# ctrl_board.net
KiCad netlist of a schematic drawn in EAGLE
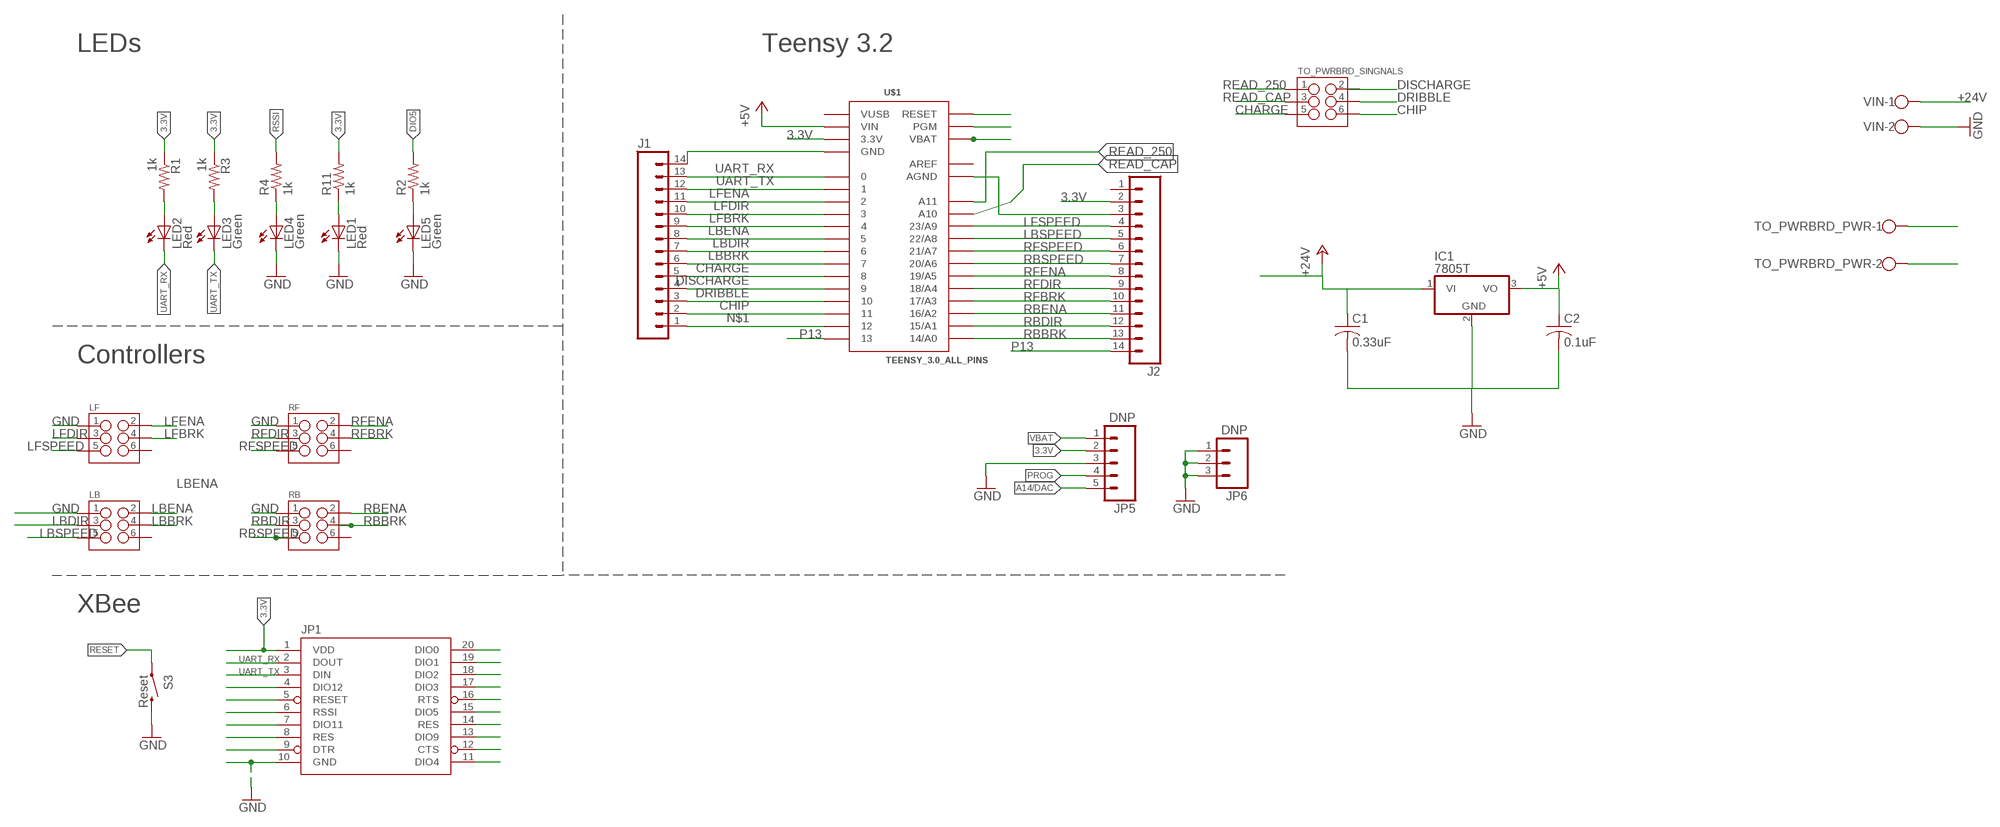
[diagram p0: schematic, sheet 1]

(export (version "E")
  (design (tool "Eeschema 10.0.6"))
  (components
    (comp (ref "C1")
      (value "0.33uF")
      (footprint "eagle-import:C0805")
      (libsource (lib "eagle-import") (part "C-USC0805"))
    )
    (comp (ref "C2")
      (value "0.1uF")
      (footprint "eagle-import:C0805")
      (libsource (lib "eagle-import") (part "C-USC0805"))
    )
    (comp (ref "IC1")
      (value "7805T")
      (footprint "eagle-import:TO220H")
      (libsource (lib "eagle-import") (part "78T05"))
    )
    (comp (ref "J1")
      (value "M14")
      (footprint "eagle-import:1X14")
      (libsource (lib "eagle-import") (part "M14"))
    )
    (comp (ref "J2")
      (value "M14")
      (footprint "eagle-import:1X14")
      (libsource (lib "eagle-import") (part "M14"))
    )
    (comp (ref "JP1")
      (value "XBEE-1B1")
      (footprint "eagle-import:XBEE-1")
      (libsource (lib "eagle-import") (part "XBEE-1B1"))
    )
    (comp (ref "JP5")
      (value "DNP")
      (footprint "eagle-import:1X05")
      (libsource (lib "eagle-import") (part "M05PTH"))
    )
    (comp (ref "JP6")
      (value "DNP")
      (footprint "eagle-import:1X03")
      (libsource (lib "eagle-import") (part "M03PTH"))
    )
    (comp (ref "LB")
      (value "M03X2POGO_PINS")
      (footprint "eagle-import:2X3_POGO")
      (libsource (lib "eagle-import") (part "M03X2POGO_PINS"))
    )
    (comp (ref "LED1")
      (value "Red")
      (footprint "eagle-import:LED-0603")
      (libsource (lib "eagle-import") (part "LED-RED0603"))
    )
    (comp (ref "LED2")
      (value "Red")
      (footprint "eagle-import:LED-0603")
      (libsource (lib "eagle-import") (part "LED-RED0603"))
    )
    (comp (ref "LED3")
      (value "Green")
      (footprint "eagle-import:LED-0603")
      (libsource (lib "eagle-import") (part "LED-GREEN0603"))
    )
    (comp (ref "LED4")
      (value "Green")
      (footprint "eagle-import:LED-0603")
      (libsource (lib "eagle-import") (part "LED-GREEN0603"))
    )
    (comp (ref "LED5")
      (value "Green")
      (footprint "eagle-import:LED-0603")
      (libsource (lib "eagle-import") (part "LED-GREEN0603"))
    )
    (comp (ref "LF")
      (value "M03X2POGO_PINS")
      (footprint "eagle-import:2X3_POGO")
      (libsource (lib "eagle-import") (part "M03X2POGO_PINS"))
    )
    (comp (ref "R1")
      (value "1k")
      (footprint "eagle-import:0603-RES")
      (libsource (lib "eagle-import") (part "1KOHM1/10W1%(0603)"))
    )
    (comp (ref "R2")
      (value "1k")
      (footprint "eagle-import:0603-RES")
      (libsource (lib "eagle-import") (part "1KOHM1/10W1%(0603)"))
    )
    (comp (ref "R3")
      (value "1k")
      (footprint "eagle-import:0603-RES")
      (libsource (lib "eagle-import") (part "1KOHM1/10W1%(0603)"))
    )
    (comp (ref "R4")
      (value "1k")
      (footprint "eagle-import:0603-RES")
      (libsource (lib "eagle-import") (part "1KOHM1/10W1%(0603)"))
    )
    (comp (ref "R11")
      (value "1k")
      (footprint "eagle-import:0603-RES")
      (libsource (lib "eagle-import") (part "1KOHM1/10W1%(0603)"))
    )
    (comp (ref "RB")
      (value "M03X2POGO_PINS")
      (footprint "eagle-import:2X3_POGO")
      (libsource (lib "eagle-import") (part "M03X2POGO_PINS"))
    )
    (comp (ref "RF")
      (value "M03X2POGO_PINS")
      (footprint "eagle-import:2X3_POGO")
      (libsource (lib "eagle-import") (part "M03X2POGO_PINS"))
    )
    (comp (ref "S3")
      (value "Reset")
      (footprint "eagle-import:TACTILE-SWITCH-SMD")
      (libsource (lib "eagle-import") (part "SWITCH-MOMENTARY-2SMD"))
    )
    (comp (ref "TO_PWRBRD_PWR")
      (value "W237-102")
      (footprint "eagle-import:W237-102")
      (fields (field (name "MPN") "237-102"))
      (libsource (lib "eagle-import") (part "W237-102"))
    )
    (comp (ref "TO_PWRBRD_SINGNALS")
      (value "M03X2POGO_PINS")
      (footprint "eagle-import:2X3_POGO")
      (libsource (lib "eagle-import") (part "M03X2POGO_PINS"))
    )
    (comp (ref "U$1")
      (value "TEENSY_3.0_ALL_PINS")
      (footprint "eagle-import:TEENSY3-ALL_PINS")
      (libsource (lib "eagle-import") (part "TEENSY_3.0_ALL_PINS"))
    )
    (comp (ref "VIN")
      (value "W237-102")
      (footprint "eagle-import:W237-102")
      (fields (field (name "MPN") "237-102"))
      (libsource (lib "eagle-import") (part "W237-102"))
    )
  )
  (nets
    (net (code "1") (name "+5V") (class "Default")
      (node (ref "C2") (pin "1") (pinfunction "1_1") (pintype "passive"))
      (node (ref "IC1") (pin "3") (pinfunction "VO_3") (pintype "passive"))
      (node (ref "U$1") (pin "VIN") (pinfunction "VIN_VIN") (pintype "power_in"))
    )
    (net (code "2") (name "+24V") (class "Default")
      (node (ref "C1") (pin "1") (pinfunction "1_1") (pintype "passive"))
      (node (ref "IC1") (pin "1") (pinfunction "VI_1") (pintype "input"))
      (node (ref "TO_PWRBRD_PWR") (pin "1") (pinfunction "KL_1") (pintype "passive"))
      (node (ref "VIN") (pin "1") (pinfunction "KL_1") (pintype "passive"))
    )
    (net (code "3") (name "/AREF") (class "Default")
      (node (ref "U$1") (pin "AREF") (pinfunction "AREF_AREF") (pintype "power_in"))
    )
    (net (code "4") (name "/CHARGE") (class "Default")
      (node (ref "J1") (pin "5") (pinfunction "5_5") (pintype "passive"))
      (node (ref "TO_PWRBRD_SINGNALS") (pin "P$5") (pinfunction "5_P$5") (pintype "bidirectional"))
      (node (ref "U$1") (pin "8") (pinfunction "8_8") (pintype "bidirectional"))
    )
    (net (code "5") (name "/CHIP") (class "Default")
      (node (ref "J1") (pin "2") (pinfunction "2_2") (pintype "passive"))
      (node (ref "TO_PWRBRD_SINGNALS") (pin "P$6") (pinfunction "6_P$6") (pintype "bidirectional"))
      (node (ref "U$1") (pin "11") (pinfunction "11_11") (pintype "bidirectional"))
    )
    (net (code "6") (name "/DISCHARGE") (class "Default")
      (node (ref "J1") (pin "4") (pinfunction "4_4") (pintype "passive"))
      (node (ref "U$1") (pin "9") (pinfunction "9_9") (pintype "bidirectional"))
    )
    (net (code "7") (name "/DRIBBLE") (class "Default")
      (node (ref "J1") (pin "3") (pinfunction "3_3") (pintype "passive"))
      (node (ref "TO_PWRBRD_SINGNALS") (pin "P$4") (pinfunction "4_P$4") (pintype "bidirectional"))
      (node (ref "U$1") (pin "10") (pinfunction "10_10") (pintype "bidirectional"))
    )
    (net (code "8") (name "/LBBRK") (class "Default")
      (node (ref "J1") (pin "6") (pinfunction "6_6") (pintype "passive"))
      (node (ref "LB") (pin "P$4") (pinfunction "4_P$4") (pintype "bidirectional"))
      (node (ref "U$1") (pin "7") (pinfunction "7_7") (pintype "bidirectional"))
    )
    (net (code "9") (name "/LBDIR") (class "Default")
      (node (ref "J1") (pin "7") (pinfunction "7_7") (pintype "passive"))
      (node (ref "LB") (pin "P$3") (pinfunction "3_P$3") (pintype "bidirectional"))
      (node (ref "U$1") (pin "6") (pinfunction "6_6") (pintype "bidirectional"))
    )
    (net (code "10") (name "/LBENA") (class "Default")
      (node (ref "J1") (pin "8") (pinfunction "8_8") (pintype "passive"))
      (node (ref "LB") (pin "P$2") (pinfunction "2_P$2") (pintype "bidirectional"))
      (node (ref "U$1") (pin "5") (pinfunction "5_5") (pintype "bidirectional"))
    )
    (net (code "11") (name "/LBSPEED") (class "Default")
      (node (ref "J2") (pin "5") (pinfunction "5_5") (pintype "passive"))
      (node (ref "LB") (pin "P$5") (pinfunction "5_P$5") (pintype "bidirectional"))
      (node (ref "U$1") (pin "22/A8") (pinfunction "22/A8_22/A8") (pintype "bidirectional"))
    )
    (net (code "12") (name "/LFBRK") (class "Default")
      (node (ref "J1") (pin "9") (pinfunction "9_9") (pintype "passive"))
      (node (ref "LF") (pin "P$4") (pinfunction "4_P$4") (pintype "bidirectional"))
      (node (ref "U$1") (pin "4") (pinfunction "4_4") (pintype "bidirectional"))
    )
    (net (code "13") (name "/LFDIR") (class "Default")
      (node (ref "J1") (pin "10") (pinfunction "10_10") (pintype "passive"))
      (node (ref "LF") (pin "P$3") (pinfunction "3_P$3") (pintype "bidirectional"))
      (node (ref "U$1") (pin "3") (pinfunction "3_3") (pintype "bidirectional"))
    )
    (net (code "14") (name "/LFENA") (class "Default")
      (node (ref "J1") (pin "11") (pinfunction "11_11") (pintype "passive"))
      (node (ref "LF") (pin "P$2") (pinfunction "2_P$2") (pintype "bidirectional"))
      (node (ref "U$1") (pin "2") (pinfunction "2_2") (pintype "bidirectional"))
    )
    (net (code "15") (name "/LFSPEED") (class "Default")
      (node (ref "J2") (pin "4") (pinfunction "4_4") (pintype "passive"))
      (node (ref "LF") (pin "P$5") (pinfunction "5_P$5") (pintype "bidirectional"))
      (node (ref "U$1") (pin "23/A9") (pinfunction "23/A9_23/A9") (pintype "bidirectional"))
    )
    (net (code "16") (name "/N$1") (class "Default")
      (node (ref "J1") (pin "1") (pinfunction "1_1") (pintype "passive"))
      (node (ref "U$1") (pin "12") (pinfunction "12_12") (pintype "bidirectional"))
    )
    (net (code "17") (name "/P13") (class "Default")
      (node (ref "J2") (pin "14") (pinfunction "14_14") (pintype "passive"))
      (node (ref "U$1") (pin "13") (pinfunction "13_13") (pintype "bidirectional"))
    )
    (net (code "18") (name "/RBBRK") (class "Default")
      (node (ref "J2") (pin "13") (pinfunction "13_13") (pintype "passive"))
      (node (ref "RB") (pin "P$4") (pinfunction "4_P$4") (pintype "bidirectional"))
      (node (ref "U$1") (pin "14/A0") (pinfunction "14/A0_14/A0") (pintype "bidirectional"))
    )
    (net (code "19") (name "/RBDIR") (class "Default")
      (node (ref "J2") (pin "12") (pinfunction "12_12") (pintype "passive"))
      (node (ref "RB") (pin "P$3") (pinfunction "3_P$3") (pintype "bidirectional"))
      (node (ref "U$1") (pin "15/A1") (pinfunction "15/A1_15/A1") (pintype "bidirectional"))
    )
    (net (code "20") (name "/RBENA") (class "Default")
      (node (ref "J2") (pin "11") (pinfunction "11_11") (pintype "passive"))
      (node (ref "RB") (pin "P$2") (pinfunction "2_P$2") (pintype "bidirectional"))
      (node (ref "U$1") (pin "16/A2") (pinfunction "16/A2_16/A2") (pintype "bidirectional"))
    )
    (net (code "21") (name "/RBSPEED") (class "Default")
      (node (ref "J2") (pin "7") (pinfunction "7_7") (pintype "passive"))
      (node (ref "RB") (pin "P$5") (pinfunction "5_P$5") (pintype "bidirectional"))
      (node (ref "U$1") (pin "20/A6") (pinfunction "20/A6_20/A6") (pintype "bidirectional"))
    )
    (net (code "22") (name "/RFBRK") (class "Default")
      (node (ref "J2") (pin "10") (pinfunction "10_10") (pintype "passive"))
      (node (ref "RF") (pin "P$4") (pinfunction "4_P$4") (pintype "bidirectional"))
      (node (ref "U$1") (pin "17/A3") (pinfunction "17/A3_17/A3") (pintype "bidirectional"))
    )
    (net (code "23") (name "/RFDIR") (class "Default")
      (node (ref "J2") (pin "9") (pinfunction "9_9") (pintype "passive"))
      (node (ref "RF") (pin "P$3") (pinfunction "3_P$3") (pintype "bidirectional"))
      (node (ref "U$1") (pin "18/A4") (pinfunction "18/A4_18/A4") (pintype "bidirectional"))
    )
    (net (code "24") (name "/RFENA") (class "Default")
      (node (ref "J2") (pin "8") (pinfunction "8_8") (pintype "passive"))
      (node (ref "RF") (pin "P$2") (pinfunction "2_P$2") (pintype "bidirectional"))
      (node (ref "U$1") (pin "19/A5") (pinfunction "19/A5_19/A5") (pintype "bidirectional"))
    )
    (net (code "25") (name "/RFSPEED") (class "Default")
      (node (ref "J2") (pin "6") (pinfunction "6_6") (pintype "passive"))
      (node (ref "RF") (pin "P$5") (pinfunction "5_P$5") (pintype "bidirectional"))
      (node (ref "U$1") (pin "21/A7") (pinfunction "21/A7_21/A7") (pintype "bidirectional"))
    )
    (net (code "26") (name "/VUSB") (class "Default")
      (node (ref "U$1") (pin "VUSB") (pinfunction "VUSB_VUSB") (pintype "power_in"))
    )
    (net (code "27") (name "3.3V") (class "Default")
      (node (ref "J2") (pin "2") (pinfunction "2_2") (pintype "passive"))
      (node (ref "JP1") (pin "1") (pinfunction "VDD_1") (pintype "power_in"))
      (node (ref "JP5") (pin "2") (pinfunction "2_2") (pintype "passive"))
      (node (ref "R1") (pin "1") (pinfunction "1_1") (pintype "passive"))
      (node (ref "R11") (pin "2") (pinfunction "2_2") (pintype "passive"))
      (node (ref "R3") (pin "1") (pinfunction "1_1") (pintype "passive"))
      (node (ref "U$1") (pin "3.3V") (pinfunction "3.3V_3.3V") (pintype "power_in"))
      (node (ref "U$1") (pin "3.3V1") (pinfunction "3.3V_3.3V1") (pintype "power_in"))
    )
    (net (code "28") (name "A14{slash}DAC") (class "Default")
      (node (ref "JP5") (pin "5") (pinfunction "5_5") (pintype "passive"))
      (node (ref "U$1") (pin "RESET/DAC") (pinfunction "RESET_RESET/DAC") (pintype "bidirectional"))
    )
    (net (code "29") (name "DIO5") (class "Default")
      (node (ref "JP1") (pin "15") (pinfunction "DIO5_15") (pintype "bidirectional"))
      (node (ref "R2") (pin "2") (pinfunction "2_2") (pintype "passive"))
    )
    (net (code "30") (name "GND") (class "Default")
      (node (ref "C1") (pin "2") (pinfunction "2_2") (pintype "passive"))
      (node (ref "C2") (pin "2") (pinfunction "2_2") (pintype "passive"))
      (node (ref "IC1") (pin "2") (pinfunction "GND_2") (pintype "passive"))
      (node (ref "J1") (pin "14") (pinfunction "14_14") (pintype "passive"))
      (node (ref "JP1") (pin "10") (pinfunction "GND_10") (pintype "power_in"))
      (node (ref "JP5") (pin "3") (pinfunction "3_3") (pintype "passive"))
      (node (ref "JP6") (pin "1") (pinfunction "1_1") (pintype "passive"))
      (node (ref "JP6") (pin "2") (pinfunction "2_2") (pintype "passive"))
      (node (ref "JP6") (pin "3") (pinfunction "3_3") (pintype "passive"))
      (node (ref "LB") (pin "P$1") (pinfunction "1_P$1") (pintype "bidirectional"))
      (node (ref "LED1") (pin "C") (pinfunction "C_C") (pintype "passive"))
      (node (ref "LED4") (pin "C") (pinfunction "C_C") (pintype "passive"))
      (node (ref "LED5") (pin "C") (pinfunction "C_C") (pintype "passive"))
      (node (ref "LF") (pin "P$1") (pinfunction "1_P$1") (pintype "bidirectional"))
      (node (ref "RB") (pin "P$1") (pinfunction "1_P$1") (pintype "bidirectional"))
      (node (ref "RF") (pin "P$1") (pinfunction "1_P$1") (pintype "bidirectional"))
      (node (ref "S3") (pin "3") (pinfunction "2_3") (pintype "passive"))
      (node (ref "TO_PWRBRD_PWR") (pin "2") (pinfunction "KL_2") (pintype "passive"))
      (node (ref "U$1") (pin "GND") (pinfunction "GND_GND") (pintype "power_in"))
      (node (ref "U$1") (pin "GND1") (pinfunction "GND_GND1") (pintype "power_in"))
      (node (ref "VIN") (pin "2") (pinfunction "KL_2") (pintype "passive"))
    )
    (net (code "31") (name "Net-(J2-Pad3)") (class "Default")
      (node (ref "J2") (pin "3") (pinfunction "3_3") (pintype "passive"))
      (node (ref "U$1") (pin "AGND") (pinfunction "AGND_AGND") (pintype "power_in"))
    )
    (net (code "32") (name "Net-(LED1-PadA)") (class "Default")
      (node (ref "LED1") (pin "A") (pinfunction "A_A") (pintype "passive"))
      (node (ref "R11") (pin "1") (pinfunction "1_1") (pintype "passive"))
    )
    (net (code "33") (name "Net-(LED2-PadA)") (class "Default")
      (node (ref "LED2") (pin "A") (pinfunction "A_A") (pintype "passive"))
      (node (ref "R1") (pin "2") (pinfunction "2_2") (pintype "passive"))
    )
    (net (code "34") (name "Net-(LED3-PadA)") (class "Default")
      (node (ref "LED3") (pin "A") (pinfunction "A_A") (pintype "passive"))
      (node (ref "R3") (pin "2") (pinfunction "2_2") (pintype "passive"))
    )
    (net (code "35") (name "Net-(LED4-PadA)") (class "Default")
      (node (ref "LED4") (pin "A") (pinfunction "A_A") (pintype "passive"))
      (node (ref "R4") (pin "1") (pinfunction "1_1") (pintype "passive"))
    )
    (net (code "36") (name "Net-(LED5-PadA)") (class "Default")
      (node (ref "LED5") (pin "A") (pinfunction "A_A") (pintype "passive"))
      (node (ref "R2") (pin "1") (pinfunction "1_1") (pintype "passive"))
    )
    (net (code "37") (name "PROG") (class "Default")
      (node (ref "JP5") (pin "4") (pinfunction "4_4") (pintype "passive"))
      (node (ref "U$1") (pin "PGM") (pinfunction "PGM_PGM") (pintype "bidirectional"))
    )
    (net (code "38") (name "READ_250") (class "Default")
      (node (ref "TO_PWRBRD_SINGNALS") (pin "P$1") (pinfunction "1_P$1") (pintype "bidirectional"))
      (node (ref "U$1") (pin "A11") (pinfunction "A11_A11") (pintype "bidirectional"))
    )
    (net (code "39") (name "READ_CAP") (class "Default")
      (node (ref "TO_PWRBRD_SINGNALS") (pin "P$3") (pinfunction "3_P$3") (pintype "bidirectional"))
      (node (ref "U$1") (pin "A10") (pinfunction "A10_A10") (pintype "bidirectional"))
    )
    (net (code "40") (name "RESET") (class "Default")
      (node (ref "JP1") (pin "5") (pinfunction "RESET_5") (pintype "input"))
      (node (ref "S3") (pin "1") (pinfunction "1_1") (pintype "passive"))
    )
    (net (code "41") (name "RSSI") (class "Default")
      (node (ref "JP1") (pin "6") (pinfunction "RSSI_6") (pintype "bidirectional"))
      (node (ref "R4") (pin "2") (pinfunction "2_2") (pintype "passive"))
    )
    (net (code "42") (name "UART_RX") (class "Default")
      (node (ref "J1") (pin "13") (pinfunction "13_13") (pintype "passive"))
      (node (ref "JP1") (pin "2") (pinfunction "DOUT_2") (pintype "output"))
      (node (ref "LED2") (pin "C") (pinfunction "C_C") (pintype "passive"))
      (node (ref "U$1") (pin "0") (pinfunction "0_0") (pintype "bidirectional"))
    )
    (net (code "43") (name "UART_TX") (class "Default")
      (node (ref "J1") (pin "12") (pinfunction "12_12") (pintype "passive"))
      (node (ref "JP1") (pin "3") (pinfunction "DIN_3") (pintype "input"))
      (node (ref "LED3") (pin "C") (pinfunction "C_C") (pintype "passive"))
      (node (ref "U$1") (pin "1") (pinfunction "1_1") (pintype "bidirectional"))
    )
    (net (code "44") (name "VBAT") (class "Default")
      (node (ref "JP5") (pin "1") (pinfunction "1_1") (pintype "passive"))
      (node (ref "U$1") (pin "VBAT") (pinfunction "VBAT_VBAT") (pintype "power_in"))
    )
    (net (code "45") (name "unconnected-(J2-Pad1)") (class "Default")
      (node (ref "J2") (pin "1") (pinfunction "1_1") (pintype "passive"))
    )
    (net (code "46") (name "unconnected-(JP1-CTS-Pad12)") (class "Default")
      (node (ref "JP1") (pin "12") (pinfunction "CTS_12") (pintype "output"))
    )
    (net (code "47") (name "unconnected-(JP1-DIO0-Pad20)") (class "Default")
      (node (ref "JP1") (pin "20") (pinfunction "DIO0_20") (pintype "bidirectional"))
    )
    (net (code "48") (name "unconnected-(JP1-DIO1-Pad19)") (class "Default")
      (node (ref "JP1") (pin "19") (pinfunction "DIO1_19") (pintype "bidirectional"))
    )
    (net (code "49") (name "unconnected-(JP1-DIO2-Pad18)") (class "Default")
      (node (ref "JP1") (pin "18") (pinfunction "DIO2_18") (pintype "bidirectional"))
    )
    (net (code "50") (name "unconnected-(JP1-DIO3-Pad17)") (class "Default")
      (node (ref "JP1") (pin "17") (pinfunction "DIO3_17") (pintype "bidirectional"))
    )
    (net (code "51") (name "unconnected-(JP1-DIO4-Pad11)") (class "Default")
      (node (ref "JP1") (pin "11") (pinfunction "DIO4_11") (pintype "bidirectional"))
    )
    (net (code "52") (name "unconnected-(JP1-DIO9-Pad13)") (class "Default")
      (node (ref "JP1") (pin "13") (pinfunction "DIO9_13") (pintype "bidirectional"))
    )
    (net (code "53") (name "unconnected-(JP1-DIO11-Pad7)") (class "Default")
      (node (ref "JP1") (pin "7") (pinfunction "DIO11_7") (pintype "bidirectional"))
    )
    (net (code "54") (name "unconnected-(JP1-DIO12-Pad4)") (class "Default")
      (node (ref "JP1") (pin "4") (pinfunction "DIO12_4") (pintype "bidirectional"))
    )
    (net (code "55") (name "unconnected-(JP1-DTR-Pad9)") (class "Default")
      (node (ref "JP1") (pin "9") (pinfunction "DTR_9") (pintype "bidirectional"))
    )
    (net (code "56") (name "unconnected-(JP1-RES-Pad8)") (class "Default")
      (node (ref "JP1") (pin "8") (pinfunction "RES_8") (pintype "bidirectional"))
    )
    (net (code "57") (name "unconnected-(JP1-RES-Pad14)") (class "Default")
      (node (ref "JP1") (pin "14") (pinfunction "RES_14") (pintype "bidirectional"))
    )
    (net (code "58") (name "unconnected-(JP1-RTS-Pad16)") (class "Default")
      (node (ref "JP1") (pin "16") (pinfunction "RTS_16") (pintype "input"))
    )
    (net (code "59") (name "unconnected-(LB-6-PadP$6)") (class "Default")
      (node (ref "LB") (pin "P$6") (pinfunction "6_P$6") (pintype "bidirectional"))
    )
    (net (code "60") (name "unconnected-(LF-6-PadP$6)") (class "Default")
      (node (ref "LF") (pin "P$6") (pinfunction "6_P$6") (pintype "bidirectional"))
    )
    (net (code "61") (name "unconnected-(RB-6-PadP$6)") (class "Default")
      (node (ref "RB") (pin "P$6") (pinfunction "6_P$6") (pintype "bidirectional"))
    )
    (net (code "62") (name "unconnected-(RF-6-PadP$6)") (class "Default")
      (node (ref "RF") (pin "P$6") (pinfunction "6_P$6") (pintype "bidirectional"))
    )
    (net (code "63") (name "unconnected-(TO_PWRBRD_SINGNALS-2-PadP$2)") (class "Default")
      (node (ref "TO_PWRBRD_SINGNALS") (pin "P$2") (pinfunction "2_P$2") (pintype "bidirectional"))
    )
  )
)
